# DIO_blk.net
KiCad netlist of a schematic drawn in Altium Designer
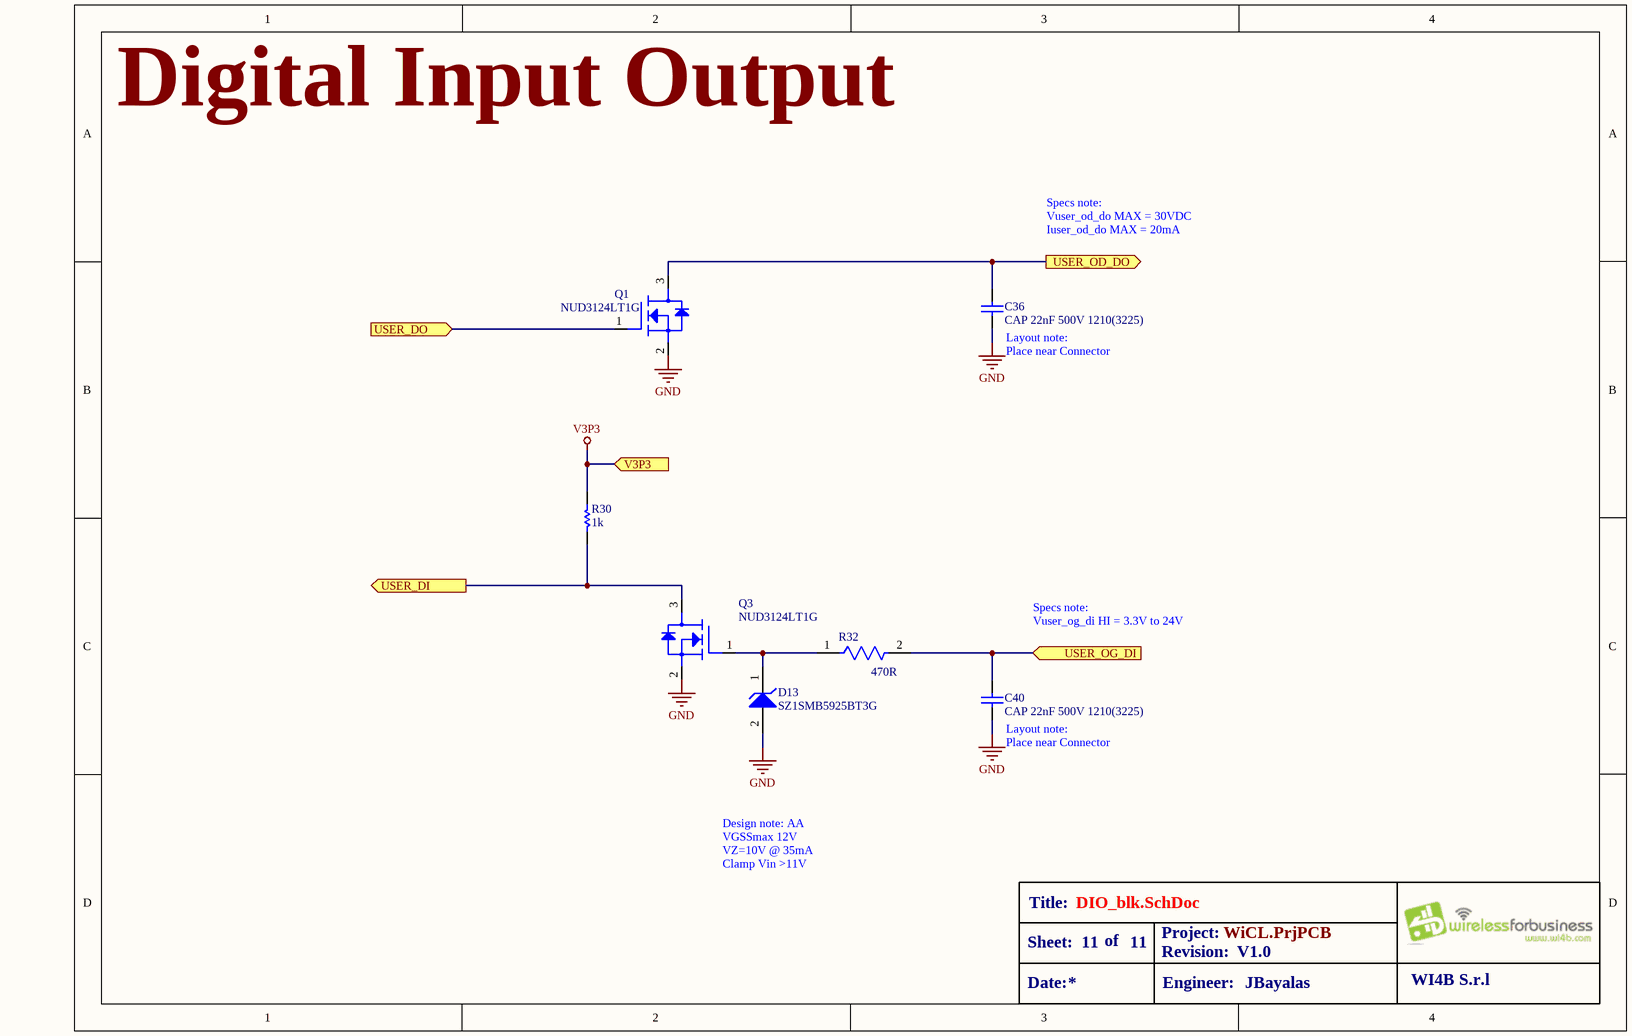
[diagram p0: DIO_blk.SchDoc]

(export (version "E")
  (design (tool "Eeschema 10.0.6"))
  (components
    (comp (ref "C36")
      (value "CAP 22nF 500V 1210(3225)")
      (footprint "CAPC1210(3225)190_N")
      (description "CAP 22nF 500V ±10% 1210 (3225 Metric) Thickness 1.9mm SMD")
      (fields (field (name "TOLERANCE") "Â±10%"))
      (libsource (lib "Altium Content Vault") (part "CAP"))
    )
    (comp (ref "C40")
      (value "CAP 22nF 500V 1210(3225)")
      (footprint "CAPC1210(3225)190_N")
      (description "CAP 22nF 500V ±10% 1210 (3225 Metric) Thickness 1.9mm SMD")
      (fields (field (name "TOLERANCE") "Â±10%"))
      (libsource (lib "Altium Content Vault") (part "CAP"))
    )
    (comp (ref "D13")
      (value "SZ1SMB5925BT3G")
      (footprint "ONSC-SMB-2-403A-03_H_V")
      (description "3 W Zener Voltage Regulator, 2-Pin SMB, Pb-Free, Tape and Reel")
      (fields (field (name "MANUFACTURER") "On Semiconductor"))
      (libsource (lib "Altium Content Vault") (part "ONSC-K1A2-2"))
    )
    (comp (ref "Q1")
      (value "NUD3124LT1G")
      (footprint "SOT-23-3")
      (description "IC INDCT LOAD DRVR AUTO SOT23")
      (fields (field (name "MPN") "NUD3124LT1G"))
      (libsource (lib "WiC_v13") (part "NUD3124LT1G"))
    )
    (comp (ref "Q3")
      (value "NUD3124LT1G")
      (footprint "SOT-23-3")
      (description "IC INDCT LOAD DRVR AUTO SOT23")
      (fields (field (name "MPN") "NUD3124LT1G"))
      (libsource (lib "WiC_v13") (part "NUD3124LT1G"))
    )
    (comp (ref "R30")
      (value "1k")
      (footprint "R0402")
      (description "RES SMD 1K OHM 1% 1/10W 0402")
      (fields (field (name "MPN") "MCS04020C1001FE000"))
      (libsource (lib "Res") (part "MCS04020C1001FE000"))
    )
    (comp (ref "R32")
      (value "CRCW2010470RJNEF")
      (footprint "FP-CRCW2010-e3-MFG")
      (description "RES Thick Film, 470Ω, 5%, 0.75W, 200ppm/°C, 2010")
      (fields (field (name "RESISTANCE") "470R") (field (name "TOLERANCE") "5%"))
      (libsource (lib "Altium Content Vault") (part "1029c3af85768c4190bb7ad29bc67b5"))
    )
  )
  (nets
    (net (code "1") (name "/USER_DI") (class "Default")
      (node (ref "Q3") (pin "3") (pinfunction "drain_3") (pintype "passive"))
      (node (ref "R30") (pin "1") (pinfunction "1_1") (pintype "passive"))
    )
    (net (code "2") (name "/USER_DO") (class "Default")
      (node (ref "Q1") (pin "1") (pinfunction "gate_1") (pintype "passive"))
    )
    (net (code "3") (name "/USER_OD_DO") (class "Default")
      (node (ref "C36") (pin "2") (pinfunction "2_2") (pintype "passive"))
      (node (ref "Q1") (pin "3") (pinfunction "drain_3") (pintype "passive"))
    )
    (net (code "4") (name "/USER_OG_DI") (class "Default")
      (node (ref "C40") (pin "2") (pinfunction "2_2") (pintype "passive"))
      (node (ref "R32") (pin "2") (pinfunction "2_2") (pintype "passive"))
    )
    (net (code "5") (name "GND") (class "Default")
      (node (ref "C36") (pin "1") (pinfunction "1_1") (pintype "passive"))
      (node (ref "C40") (pin "1") (pinfunction "1_1") (pintype "passive"))
      (node (ref "D13") (pin "2") (pinfunction "A_2") (pintype "passive"))
      (node (ref "Q1") (pin "2") (pinfunction "source_2") (pintype "passive"))
      (node (ref "Q3") (pin "2") (pinfunction "source_2") (pintype "passive"))
    )
    (net (code "6") (name "Net-(D13-K)") (class "Default")
      (node (ref "D13") (pin "1") (pinfunction "K_1") (pintype "passive"))
      (node (ref "Q3") (pin "1") (pinfunction "gate_1") (pintype "passive"))
      (node (ref "R32") (pin "1") (pinfunction "1_1") (pintype "passive"))
    )
    (net (code "7") (name "V3P3") (class "Default")
      (node (ref "R30") (pin "2") (pinfunction "2_2") (pintype "passive"))
    )
  )
)
